# tent2.net
KiCad netlist of a schematic drawn in EAGLE
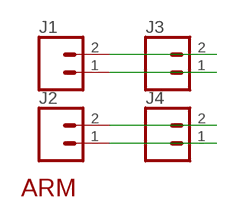
[diagram p0: schematic, sheet 1]

(export (version "E")
  (design (tool "Eeschema 10.0.6"))
  (components
    (comp (ref "J1")
      (value "CONN_02LOCK")
      (footprint "eagle-import:1X02_LOCK")
      (libsource (lib "eagle-import") (part "CONN_02LOCK"))
    )
    (comp (ref "J2")
      (value "CONN_02LOCK")
      (footprint "eagle-import:1X02_LOCK")
      (libsource (lib "eagle-import") (part "CONN_02LOCK"))
    )
    (comp (ref "J3")
      (value "CONN_02LOCK")
      (footprint "eagle-import:1X02_LOCK")
      (libsource (lib "eagle-import") (part "CONN_02LOCK"))
    )
    (comp (ref "J4")
      (value "CONN_02LOCK")
      (footprint "eagle-import:1X02_LOCK")
      (libsource (lib "eagle-import") (part "CONN_02LOCK"))
    )
    (comp (ref "U$1")
      (value "ARMTENT2")
      (footprint "eagle-import:TENT2")
      (libsource (lib "eagle-import") (part "ARMTENT2"))
    )
  )
  (nets
    (net (code "1") (name "Net-(J1-Pad1)") (class "Default")
      (node (ref "J1") (pin "1") (pinfunction "1_1") (pintype "passive"))
      (node (ref "J3") (pin "1") (pinfunction "1_1") (pintype "passive"))
    )
    (net (code "2") (name "Net-(J1-Pad2)") (class "Default")
      (node (ref "J1") (pin "2") (pinfunction "2_2") (pintype "passive"))
      (node (ref "J3") (pin "2") (pinfunction "2_2") (pintype "passive"))
    )
    (net (code "3") (name "Net-(J2-Pad1)") (class "Default")
      (node (ref "J2") (pin "1") (pinfunction "1_1") (pintype "passive"))
      (node (ref "J4") (pin "1") (pinfunction "1_1") (pintype "passive"))
    )
    (net (code "4") (name "Net-(J2-Pad2)") (class "Default")
      (node (ref "J2") (pin "2") (pinfunction "2_2") (pintype "passive"))
      (node (ref "J4") (pin "2") (pinfunction "2_2") (pintype "passive"))
    )
  )
)
